# main.net
KiCad netlist of a schematic drawn in Altium Designer
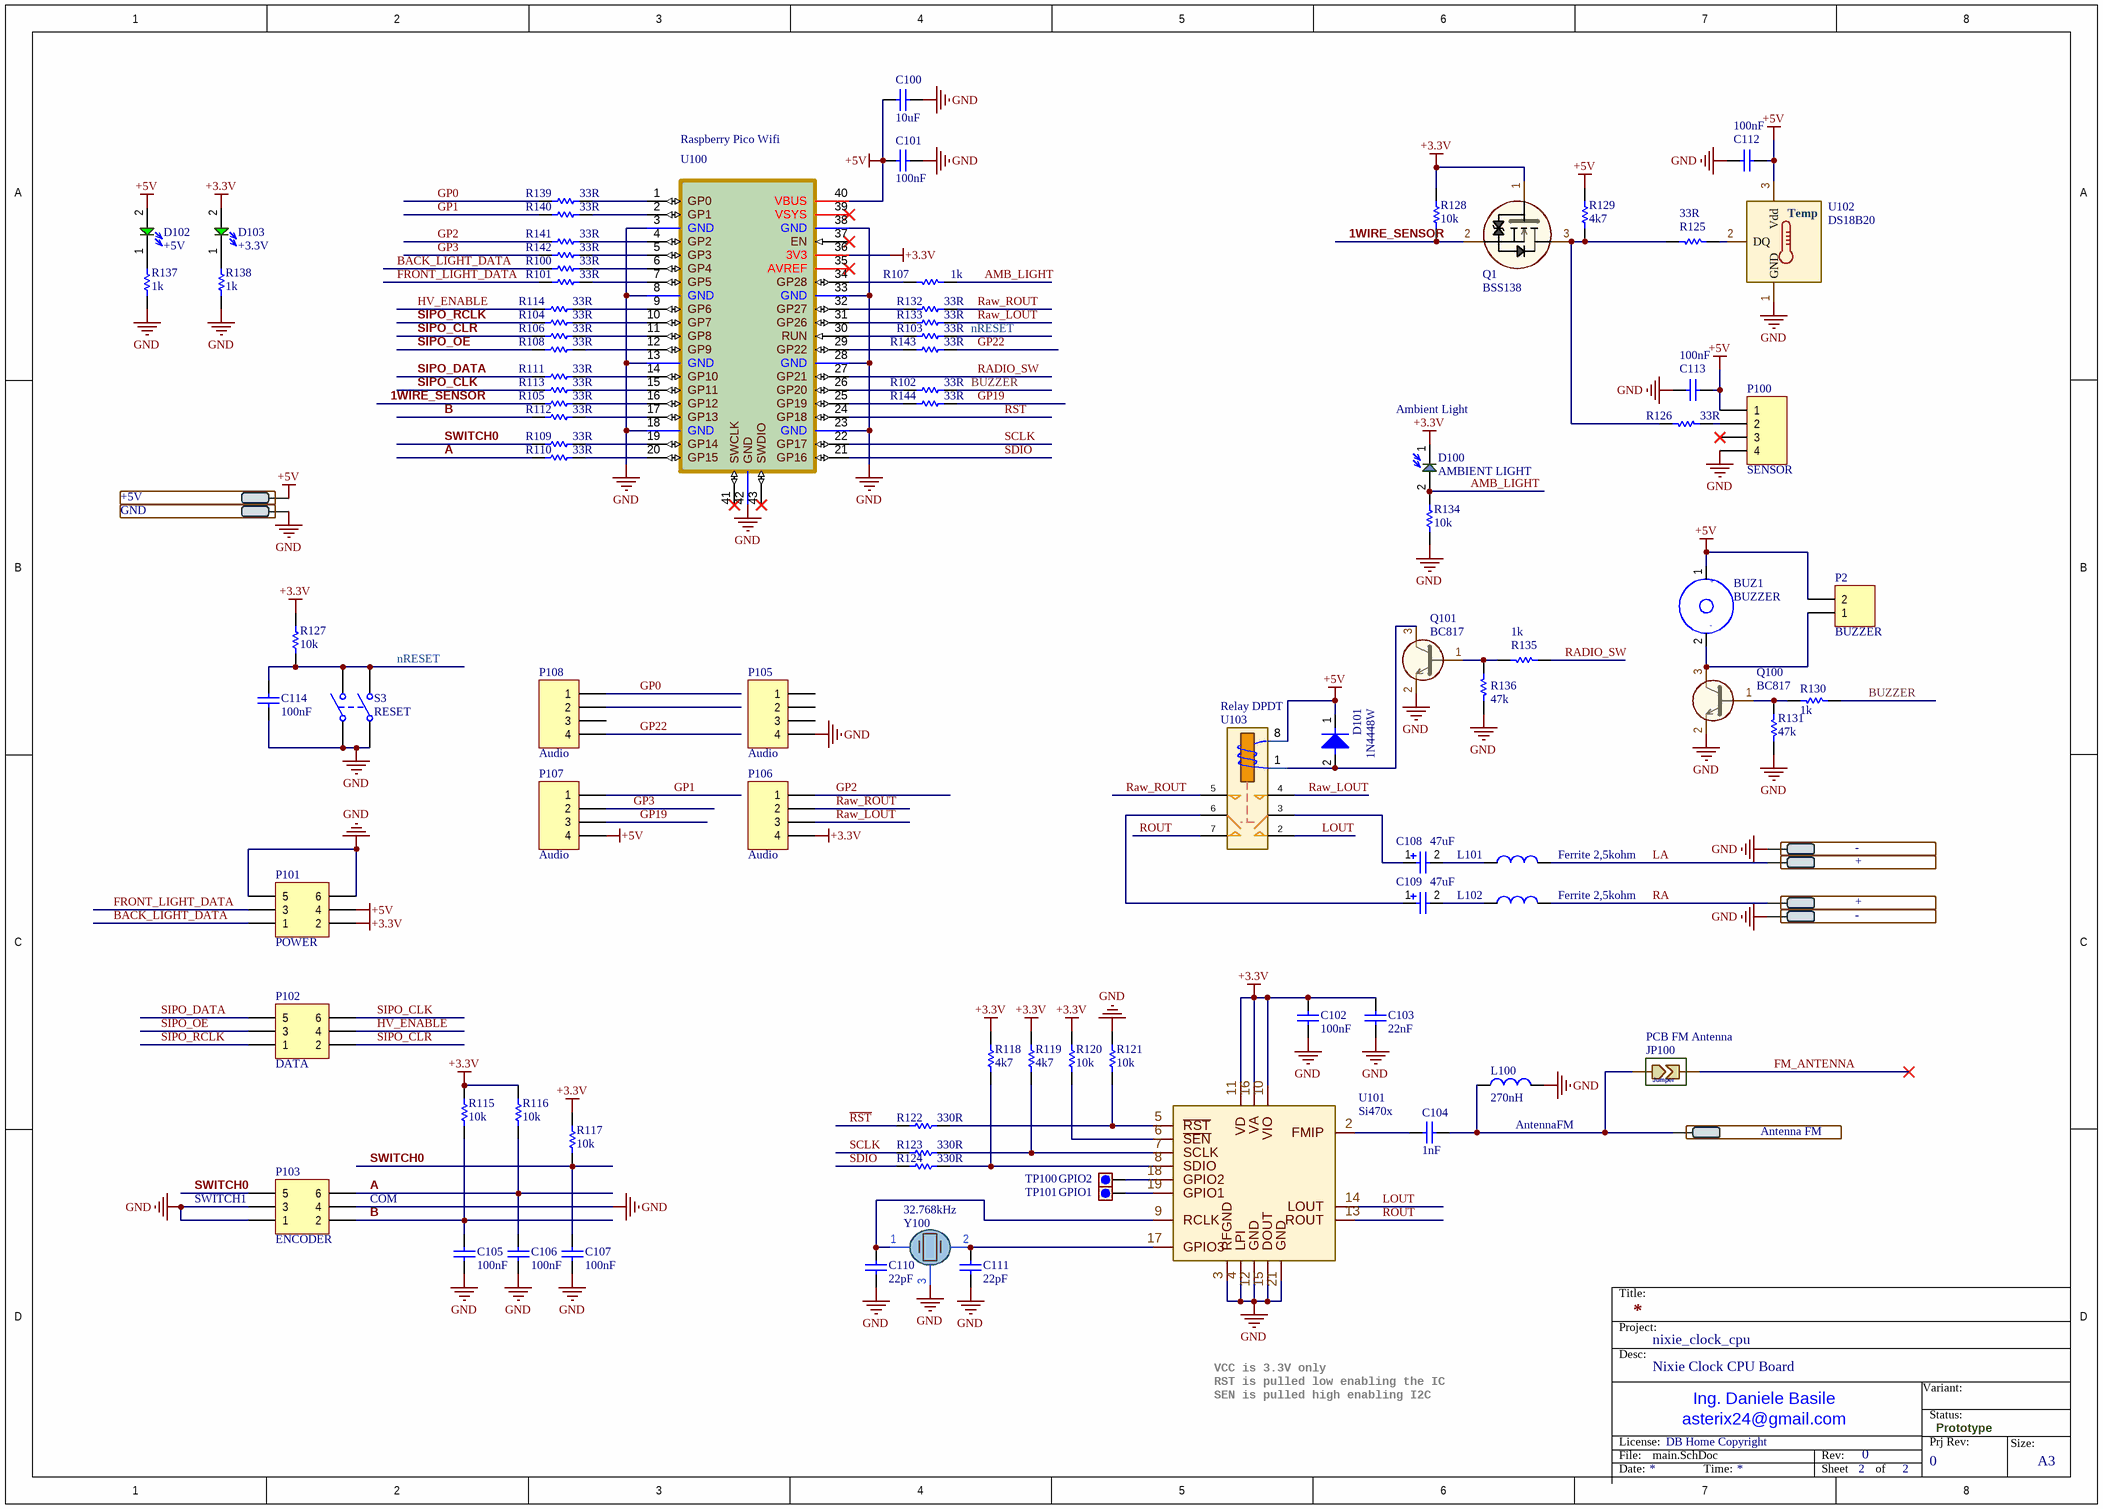
[diagram p0: main.SchDoc]

(export (version "E")
  (design (tool "Eeschema 10.0.6"))
  (components
    (comp (ref "BUZ1")
      (value "BUZZER")
      (footprint "buzzer_14mm_thd")
      (libsource (lib "develer_library") (part "BUZZER"))
    )
    (comp (ref "C100")
      (value "10uF")
      (footprint "0603_[1608]")
      (description "Capacitor")
      (libsource (lib "develer_generic") (part "Cap"))
    )
    (comp (ref "C101")
      (value "100nF")
      (footprint "0603_[1608]")
      (description "Capacitor")
      (libsource (lib "develer_generic") (part "Cap"))
    )
    (comp (ref "C102")
      (value "100nF")
      (footprint "0603_[1608]")
      (description "Capacitor")
      (libsource (lib "develer_generic") (part "Cap"))
    )
    (comp (ref "C103")
      (value "22nF")
      (footprint "0603_[1608]")
      (description "Capacitor")
      (libsource (lib "develer_generic") (part "Cap"))
    )
    (comp (ref "C104")
      (value "1nF")
      (footprint "0603_[1608]")
      (description "Capacitor")
      (libsource (lib "develer_generic") (part "Cap"))
    )
    (comp (ref "C105")
      (value "100nF")
      (footprint "0603_[1608]")
      (description "Capacitor")
      (libsource (lib "develer_generic") (part "Cap"))
    )
    (comp (ref "C106")
      (value "100nF")
      (footprint "0603_[1608]")
      (description "Capacitor")
      (libsource (lib "develer_generic") (part "Cap"))
    )
    (comp (ref "C107")
      (value "100nF")
      (footprint "0603_[1608]")
      (description "Capacitor")
      (libsource (lib "develer_generic") (part "Cap"))
    )
    (comp (ref "C108")
      (value "47uF")
      (footprint "[7343]_CAP_TAN_1P_2N")
      (description "Capacitor")
      (libsource (lib "develer_generic") (part "CapPol"))
    )
    (comp (ref "C109")
      (value "47uF")
      (footprint "[7343]_CAP_TAN_1P_2N")
      (description "Capacitor")
      (libsource (lib "develer_generic") (part "CapPol"))
    )
    (comp (ref "C110")
      (value "22pF")
      (footprint "0603_[1608]")
      (description "Capacitor")
      (libsource (lib "develer_generic") (part "Cap"))
    )
    (comp (ref "C111")
      (value "22pF")
      (footprint "0603_[1608]")
      (description "Capacitor")
      (libsource (lib "develer_generic") (part "Cap"))
    )
    (comp (ref "C112")
      (value "100nF")
      (footprint "0603_[1608]")
      (description "Capacitor")
      (libsource (lib "develer_generic") (part "Cap"))
    )
    (comp (ref "C113")
      (value "100nF")
      (footprint "0603_[1608]")
      (description "Capacitor")
      (libsource (lib "develer_generic") (part "Cap"))
    )
    (comp (ref "C114")
      (value "100nF")
      (footprint "0603_[1608]")
      (description "Capacitor")
      (libsource (lib "develer_generic") (part "Cap"))
    )
    (comp (ref "D100")
      (value "AMBIENT LIGHT")
      (footprint "R5_LED_THD_A2-K1")
      (description "Diode Led")
      (fields (field (name "PUBLISHER") "Develer srl"))
      (libsource (lib "develer_generic") (part "PhotoDiode"))
    )
    (comp (ref "D101")
      (value "1N4448W")
      (footprint "SOD-123_K1-A2")
      (description "Diode, Rectifier, 0,5A, 30V min (MBR230LSFT1G; Rohm RB070MM-30TR; panjin SBA130ASR100001)")
      (libsource (lib "develer_library") (part "Diode"))
    )
    (comp (ref "D102")
      (value "+5V")
      (footprint "0603_[1608]_K1-A2_LED")
      (description "Diode Led")
      (fields (field (name "PUBLISHER") "Develer srl"))
      (libsource (lib "develer_generic") (part "DiodeLedSmall_GREEN"))
    )
    (comp (ref "D103")
      (value "+3.3V")
      (footprint "0603_[1608]_K1-A2_LED")
      (description "Diode Led")
      (fields (field (name "PUBLISHER") "Develer srl"))
      (libsource (lib "develer_generic") (part "DiodeLedSmall_GREEN"))
    )
    (comp (ref "J100")
      (value "Antenna FM")
      (footprint "SMD_PIN_2x5MM")
      (description "Solder pad")
      (fields (field (name "PUBLISHER") "Develer srl"))
      (libsource (lib "develer_generic") (part "SolderPad"))
    )
    (comp (ref "J101")
      (value "-")
      (footprint "SMD_PIN_2x5MM")
      (description "Solder pad")
      (fields (field (name "PUBLISHER") "Develer srl"))
      (libsource (lib "develer_generic") (part "SolderPad"))
    )
    (comp (ref "J102")
      (value "+")
      (footprint "SMD_PIN_2x5MM")
      (description "Solder pad")
      (fields (field (name "PUBLISHER") "Develer srl"))
      (libsource (lib "develer_generic") (part "SolderPad"))
    )
    (comp (ref "J103")
      (value "+")
      (footprint "SMD_PIN_2x5MM")
      (description "Solder pad")
      (fields (field (name "PUBLISHER") "Develer srl"))
      (libsource (lib "develer_generic") (part "SolderPad"))
    )
    (comp (ref "J104")
      (value "-")
      (footprint "SMD_PIN_2x5MM")
      (description "Solder pad")
      (fields (field (name "PUBLISHER") "Develer srl"))
      (libsource (lib "develer_generic") (part "SolderPad"))
    )
    (comp (ref "J105")
      (value "+5V")
      (footprint "SMD_PIN_2x5MM")
      (description "Solder pad")
      (fields (field (name "PUBLISHER") "Develer srl"))
      (libsource (lib "develer_generic") (part "SolderPad"))
    )
    (comp (ref "J106")
      (value "GND")
      (footprint "SMD_PIN_2x5MM")
      (description "Solder pad")
      (fields (field (name "PUBLISHER") "Develer srl"))
      (libsource (lib "develer_generic") (part "SolderPad"))
    )
    (comp (ref "JP100")
      (value "PCB FM Antenna")
      (footprint "0603_[1608]_JUMPER")
      (description "Jumper SMD")
      (fields (field (name "PUBLISHER") "Develer srl"))
      (libsource (lib "develer_generic") (part "JumperSMD"))
    )
    (comp (ref "L100")
      (value "270nH")
      (footprint "0603_[1608]")
      (description "ComponetDescritions (altrenative1; alternativ2)")
      (fields (field (name "PUBLISHER") "Develer srl"))
      (libsource (lib "develer_generic") (part "Inductor"))
    )
    (comp (ref "L101")
      (value "Ferrite 2,5kohm")
      (footprint "0603_[1608]")
      (description "BLM18BD252SN1D")
      (fields (field (name "PUBLISHER") "Develer srl"))
      (libsource (lib "develer_generic") (part "Inductor"))
    )
    (comp (ref "L102")
      (value "Ferrite 2,5kohm")
      (footprint "0603_[1608]")
      (description "BLM18BD252SN1D")
      (fields (field (name "PUBLISHER") "Develer srl"))
      (libsource (lib "develer_generic") (part "Inductor"))
    )
    (comp (ref "P2")
      (value "BUZZER")
      (footprint "HEADER_1X2_2.54MM_THD")
      (description "Pin Header, 2pin, 2.54mm")
      (fields (field (name "PUBLISHER") "Altium Limited"))
      (libsource (lib "Miscellaneous Connectors") (part "Header 2"))
    )
    (comp (ref "P100")
      (value "SENSOR")
      (footprint "HEADER_1X4_2.54MM_THD")
      (description "Header, 4-Pin")
      (fields (field (name "PUBLISHER") "Altium Limited"))
      (libsource (lib "Miscellaneous Connectors") (part "Header 4"))
    )
    (comp (ref "P101")
      (value "POWER")
      (footprint "SOCKET_2x3_2.54mm_THD")
      (description "Header, 3-Pin, Dual row")
      (fields (field (name "PUBLISHER") "Altium Limited"))
      (libsource (lib "Miscellaneous Connectors") (part "Header 3X2"))
    )
    (comp (ref "P102")
      (value "DATA")
      (footprint "SOCKET_2x3_2.54mm_THD")
      (description "Header, 3-Pin, Dual row")
      (fields (field (name "PUBLISHER") "Altium Limited"))
      (libsource (lib "Miscellaneous Connectors") (part "Header 3X2"))
    )
    (comp (ref "P103")
      (value "ENCODER")
      (footprint "SOCKET_2x3_2.54mm_THD")
      (description "Header, 3-Pin, Dual row")
      (fields (field (name "PUBLISHER") "Altium Limited"))
      (libsource (lib "Miscellaneous Connectors") (part "Header 3X2"))
    )
    (comp (ref "P105")
      (value "Audio")
      (footprint "HEADER_1X4_2.54MM_THD")
      (description "Header, 4-Pin")
      (fields (field (name "PUBLISHER") "Altium Limited"))
      (libsource (lib "") (part "Header 4_1"))
    )
    (comp (ref "P106")
      (value "Audio")
      (footprint "HEADER_1X4_2.54MM_THD")
      (description "Header, 4-Pin")
      (fields (field (name "PUBLISHER") "Altium Limited"))
      (libsource (lib "") (part "Header 4_1"))
    )
    (comp (ref "P107")
      (value "Audio")
      (footprint "HEADER_1X4_2.54MM_THD")
      (description "Header, 4-Pin")
      (fields (field (name "PUBLISHER") "Altium Limited"))
      (libsource (lib "") (part "Header 4_1"))
    )
    (comp (ref "P108")
      (value "Audio")
      (footprint "HEADER_1X4_2.54MM_THD")
      (description "Header, 4-Pin")
      (fields (field (name "PUBLISHER") "Altium Limited"))
      (libsource (lib "") (part "Header 4_1"))
    )
    (comp (ref "Q1")
      (value "BSS138")
      (footprint "SOT-23")
      (description "N-MOSFET 50V 0,22A")
      (fields (field (name "PUBLISHER") "Develer srl"))
      (libsource (lib "develer_components") (part "BSS138"))
    )
    (comp (ref "Q100")
      (value "BC817")
      (footprint "SOT-23")
      (description "Transistor BJT NPN")
      (fields (field (name "PUBLISHER") "Develer srl"))
      (libsource (lib "develer_generic") (part "NPN_3P"))
    )
    (comp (ref "Q101")
      (value "BC817")
      (footprint "SOT-23")
      (description "Transistor BJT NPN")
      (fields (field (name "PUBLISHER") "Develer srl"))
      (libsource (lib "develer_generic") (part "NPN_3P"))
    )
    (comp (ref "R100")
      (value "33R")
      (footprint "0603_[1608]")
      (description "Resistor")
      (fields (field (name "PUBLISHER") "Develer srl"))
      (libsource (lib "develer_generic") (part "Res"))
    )
    (comp (ref "R101")
      (value "33R")
      (footprint "0603_[1608]")
      (description "Resistor")
      (fields (field (name "PUBLISHER") "Develer srl"))
      (libsource (lib "develer_generic") (part "Res"))
    )
    (comp (ref "R102")
      (value "33R")
      (footprint "0603_[1608]")
      (description "Resistor")
      (fields (field (name "PUBLISHER") "Develer srl"))
      (libsource (lib "develer_generic") (part "Res"))
    )
    (comp (ref "R103")
      (value "33R")
      (footprint "0603_[1608]")
      (description "Resistor")
      (fields (field (name "PUBLISHER") "Develer srl"))
      (libsource (lib "develer_generic") (part "Res"))
    )
    (comp (ref "R104")
      (value "33R")
      (footprint "0603_[1608]")
      (description "Resistor")
      (fields (field (name "PUBLISHER") "Develer srl"))
      (libsource (lib "develer_generic") (part "Res"))
    )
    (comp (ref "R105")
      (value "33R")
      (footprint "0603_[1608]")
      (description "Resistor")
      (fields (field (name "PUBLISHER") "Develer srl"))
      (libsource (lib "develer_generic") (part "Res"))
    )
    (comp (ref "R106")
      (value "33R")
      (footprint "0603_[1608]")
      (description "Resistor")
      (fields (field (name "PUBLISHER") "Develer srl"))
      (libsource (lib "develer_generic") (part "Res"))
    )
    (comp (ref "R107")
      (value "1k")
      (footprint "0603_[1608]")
      (description "Resistor")
      (fields (field (name "PUBLISHER") "Develer srl"))
      (libsource (lib "develer_generic") (part "Res"))
    )
    (comp (ref "R108")
      (value "33R")
      (footprint "0603_[1608]")
      (description "Resistor")
      (fields (field (name "PUBLISHER") "Develer srl"))
      (libsource (lib "develer_generic") (part "Res"))
    )
    (comp (ref "R109")
      (value "33R")
      (footprint "0603_[1608]")
      (description "Resistor")
      (fields (field (name "PUBLISHER") "Develer srl"))
      (libsource (lib "develer_generic") (part "Res"))
    )
    (comp (ref "R110")
      (value "33R")
      (footprint "0603_[1608]")
      (description "Resistor")
      (fields (field (name "PUBLISHER") "Develer srl"))
      (libsource (lib "develer_generic") (part "Res"))
    )
    (comp (ref "R111")
      (value "33R")
      (footprint "0603_[1608]")
      (description "Resistor")
      (fields (field (name "PUBLISHER") "Develer srl"))
      (libsource (lib "develer_generic") (part "Res"))
    )
    (comp (ref "R112")
      (value "33R")
      (footprint "0603_[1608]")
      (description "Resistor")
      (fields (field (name "PUBLISHER") "Develer srl"))
      (libsource (lib "develer_generic") (part "Res"))
    )
    (comp (ref "R113")
      (value "33R")
      (footprint "0603_[1608]")
      (description "Resistor")
      (fields (field (name "PUBLISHER") "Develer srl"))
      (libsource (lib "develer_generic") (part "Res"))
    )
    (comp (ref "R114")
      (value "33R")
      (footprint "0603_[1608]")
      (description "Resistor")
      (fields (field (name "PUBLISHER") "Develer srl"))
      (libsource (lib "develer_generic") (part "Res"))
    )
    (comp (ref "R115")
      (value "10k")
      (footprint "0603_[1608]")
      (description "Resistor")
      (fields (field (name "PUBLISHER") "Develer srl"))
      (libsource (lib "develer_generic") (part "Res"))
    )
    (comp (ref "R116")
      (value "10k")
      (footprint "0603_[1608]")
      (description "Resistor")
      (fields (field (name "PUBLISHER") "Develer srl"))
      (libsource (lib "develer_generic") (part "Res"))
    )
    (comp (ref "R117")
      (value "10k")
      (footprint "0603_[1608]")
      (description "Resistor")
      (fields (field (name "PUBLISHER") "Develer srl"))
      (libsource (lib "develer_generic") (part "Res"))
    )
    (comp (ref "R118")
      (value "4k7")
      (footprint "0603_[1608]")
      (description "Resistor")
      (fields (field (name "PUBLISHER") "Develer srl"))
      (libsource (lib "develer_generic") (part "Res"))
    )
    (comp (ref "R119")
      (value "4k7")
      (footprint "0603_[1608]")
      (description "Resistor")
      (fields (field (name "PUBLISHER") "Develer srl"))
      (libsource (lib "develer_generic") (part "Res"))
    )
    (comp (ref "R120")
      (value "10k")
      (footprint "0603_[1608]")
      (description "Resistor")
      (fields (field (name "PUBLISHER") "Develer srl"))
      (libsource (lib "develer_generic") (part "Res"))
    )
    (comp (ref "R121")
      (value "10k")
      (footprint "0603_[1608]")
      (description "Resistor")
      (fields (field (name "PUBLISHER") "Develer srl"))
      (libsource (lib "develer_generic") (part "Res"))
    )
    (comp (ref "R122")
      (value "330R")
      (footprint "0603_[1608]")
      (description "Resistor")
      (fields (field (name "PUBLISHER") "Develer srl"))
      (libsource (lib "develer_generic") (part "Res"))
    )
    (comp (ref "R123")
      (value "330R")
      (footprint "0603_[1608]")
      (description "Resistor")
      (fields (field (name "PUBLISHER") "Develer srl"))
      (libsource (lib "develer_generic") (part "Res"))
    )
    (comp (ref "R124")
      (value "330R")
      (footprint "0603_[1608]")
      (description "Resistor")
      (fields (field (name "PUBLISHER") "Develer srl"))
      (libsource (lib "develer_generic") (part "Res"))
    )
    (comp (ref "R125")
      (value "33R")
      (footprint "0603_[1608]")
      (description "Resistor")
      (fields (field (name "PUBLISHER") "Develer srl"))
      (libsource (lib "develer_generic") (part "Res"))
    )
    (comp (ref "R126")
      (value "33R")
      (footprint "0603_[1608]")
      (description "Resistor")
      (fields (field (name "PUBLISHER") "Develer srl"))
      (libsource (lib "develer_generic") (part "Res"))
    )
    (comp (ref "R127")
      (value "10k")
      (footprint "0603_[1608]")
      (description "Resistor")
      (fields (field (name "PUBLISHER") "Develer srl"))
      (libsource (lib "develer_generic") (part "Res"))
    )
    (comp (ref "R128")
      (value "10k")
      (footprint "0603_[1608]")
      (description "Resistor")
      (fields (field (name "PUBLISHER") "Develer srl"))
      (libsource (lib "develer_generic") (part "Res"))
    )
    (comp (ref "R129")
      (value "4k7")
      (footprint "0603_[1608]")
      (description "Resistor")
      (fields (field (name "PUBLISHER") "Develer srl"))
      (libsource (lib "develer_generic") (part "Res"))
    )
    (comp (ref "R130")
      (value "1k")
      (footprint "0603_[1608]")
      (description "Resistor")
      (fields (field (name "PUBLISHER") "Develer srl"))
      (libsource (lib "develer_generic") (part "Res"))
    )
    (comp (ref "R131")
      (value "47k")
      (footprint "0603_[1608]")
      (description "Resistor")
      (fields (field (name "PUBLISHER") "Develer srl"))
      (libsource (lib "develer_generic") (part "Res"))
    )
    (comp (ref "R132")
      (value "33R")
      (footprint "0603_[1608]")
      (description "Resistor")
      (fields (field (name "PUBLISHER") "Develer srl"))
      (libsource (lib "develer_generic") (part "Res"))
    )
    (comp (ref "R133")
      (value "33R")
      (footprint "0603_[1608]")
      (description "Resistor")
      (fields (field (name "PUBLISHER") "Develer srl"))
      (libsource (lib "develer_generic") (part "Res"))
    )
    (comp (ref "R134")
      (value "10k")
      (footprint "0603_[1608]")
      (description "Resistor")
      (fields (field (name "PUBLISHER") "Develer srl"))
      (libsource (lib "develer_generic") (part "Res"))
    )
    (comp (ref "R135")
      (value "1k")
      (footprint "0603_[1608]")
      (description "Resistor")
      (fields (field (name "PUBLISHER") "Develer srl"))
      (libsource (lib "develer_generic") (part "Res"))
    )
    (comp (ref "R136")
      (value "47k")
      (footprint "0603_[1608]")
      (description "Resistor")
      (fields (field (name "PUBLISHER") "Develer srl"))
      (libsource (lib "develer_generic") (part "Res"))
    )
    (comp (ref "R137")
      (value "1k")
      (footprint "0603_[1608]")
      (description "Resistor")
      (fields (field (name "PUBLISHER") "Develer srl"))
      (libsource (lib "develer_generic") (part "Res"))
    )
    (comp (ref "R138")
      (value "1k")
      (footprint "0603_[1608]")
      (description "Resistor")
      (fields (field (name "PUBLISHER") "Develer srl"))
      (libsource (lib "develer_generic") (part "Res"))
    )
    (comp (ref "R139")
      (value "33R")
      (footprint "0603_[1608]")
      (description "Resistor")
      (fields (field (name "PUBLISHER") "Develer srl"))
      (libsource (lib "develer_generic") (part "Res"))
    )
    (comp (ref "R140")
      (value "33R")
      (footprint "0603_[1608]")
      (description "Resistor")
      (fields (field (name "PUBLISHER") "Develer srl"))
      (libsource (lib "develer_generic") (part "Res"))
    )
    (comp (ref "R141")
      (value "33R")
      (footprint "0603_[1608]")
      (description "Resistor")
      (fields (field (name "PUBLISHER") "Develer srl"))
      (libsource (lib "develer_generic") (part "Res"))
    )
    (comp (ref "R142")
      (value "33R")
      (footprint "0603_[1608]")
      (description "Resistor")
      (fields (field (name "PUBLISHER") "Develer srl"))
      (libsource (lib "develer_generic") (part "Res"))
    )
    (comp (ref "R143")
      (value "33R")
      (footprint "0603_[1608]")
      (description "Resistor")
      (fields (field (name "PUBLISHER") "Develer srl"))
      (libsource (lib "develer_generic") (part "Res"))
    )
    (comp (ref "R144")
      (value "33R")
      (footprint "0603_[1608]")
      (description "Resistor")
      (fields (field (name "PUBLISHER") "Develer srl"))
      (libsource (lib "develer_generic") (part "Res"))
    )
    (comp (ref "S3")
      (value "RESET")
      (footprint "TACTILE_SWITCH_6x6MM_THD")
      (description "Double-Pole, Single-Throw Switch")
      (fields (field (name "PUBLISHER") "Altium Limited"))
      (libsource (lib "develer_generic") (part "Switch DPST"))
    )
    (comp (ref "TP100")
      (value "GPIO2")
      (footprint "TEST_POINT_THD_D1.6MM")
      (description "TestPoint")
      (fields (field (name "PUBLISHER") "Develer srl"))
      (libsource (lib "develer_generic") (part "TestPoint"))
    )
    (comp (ref "TP101")
      (value "GPIO1")
      (footprint "TEST_POINT_THD_D1.6MM")
      (description "TestPoint")
      (fields (field (name "PUBLISHER") "Develer srl"))
      (libsource (lib "develer_generic") (part "TestPoint"))
    )
    (comp (ref "U100")
      (value "Raspberry Pico Wifi")
      (footprint "RasberryPicoMod")
      (description "Raspberry PICO som module")
      (fields (field (name "PUBLISHER") "Develer srl"))
      (libsource (lib "develer_components") (part "RaspberryPico_Mod"))
    )
    (comp (ref "U101")
      (value "Si470x")
      (footprint "QFN-50P-20_PAD")
      (description "Full FM radio whit RDS")
      (fields (field (name "PUBLISHER") "Develer srl"))
      (libsource (lib "develer_components") (part "Si470x"))
    )
    (comp (ref "U102")
      (value "DS18B20")
      (footprint "develer_misc:TO-92")
      (description "Programmable Resolution 1-Wire Digital Thermometer")
      (fields (field (name "PUBLISHER") "Develer srl"))
      (libsource (lib "develer_components") (part "DS18B20"))
    )
    (comp (ref "U103")
      (value "Relay DPDT")
      (footprint "RELAYS_DPST_THD_6x10_5.08mm")
      (fields (field (name "PUBLISHER") "Develer srl"))
      (libsource (lib "develer_generic") (part "Relay2_DPDT"))
    )
    (comp (ref "Y100")
      (value "32.768kHz")
      (footprint "CRISTAL_R26_PAD")
      (description "ComponentDescriptions (altrenative1; alternative2)")
      (fields (field (name "PUBLISHER") "Develer srl"))
      (libsource (lib "develer_generic") (part "Cristal_3P"))
    )
  )
  (nets
    (net (code "1") (name "+3.3V") (class "Default")
      (node (ref "C102") (pin "2") (pinfunction "2_2") (pintype "passive"))
      (node (ref "C103") (pin "2") (pinfunction "2_2") (pintype "passive"))
      (node (ref "D100") (pin "1") (pinfunction "K_1") (pintype "passive"))
      (node (ref "D103") (pin "2") (pinfunction "A_2") (pintype "passive"))
      (node (ref "P101") (pin "2") (pinfunction "2_2") (pintype "passive"))
      (node (ref "P106") (pin "4") (pinfunction "4_4") (pintype "passive"))
      (node (ref "Q1") (pin "1") (pinfunction "G_1") (pintype "passive"))
      (node (ref "R115") (pin "1") (pinfunction "1_1") (pintype "passive"))
      (node (ref "R116") (pin "1") (pinfunction "1_1") (pintype "passive"))
      (node (ref "R117") (pin "1") (pinfunction "1_1") (pintype "passive"))
      (node (ref "R118") (pin "1") (pinfunction "1_1") (pintype "passive"))
      (node (ref "R119") (pin "1") (pinfunction "1_1") (pintype "passive"))
      (node (ref "R120") (pin "1") (pinfunction "1_1") (pintype "passive"))
      (node (ref "R127") (pin "1") (pinfunction "1_1") (pintype "passive"))
      (node (ref "R128") (pin "1") (pinfunction "1_1") (pintype "passive"))
      (node (ref "U100") (pin "36") (pinfunction "3V3_36") (pintype "power_in"))
      (node (ref "U101") (pin "10") (pinfunction "VIO_10") (pintype "passive"))
      (node (ref "U101") (pin "11") (pinfunction "VD_11") (pintype "passive"))
      (node (ref "U101") (pin "16") (pinfunction "VA_16") (pintype "passive"))
    )
    (net (code "2") (name "+5V") (class "Default")
      (node (ref "BUZ1") (pin "1") (pinfunction "1_1") (pintype "passive"))
      (node (ref "C100") (pin "1") (pinfunction "1_1") (pintype "passive"))
      (node (ref "C101") (pin "1") (pinfunction "1_1") (pintype "passive"))
      (node (ref "C112") (pin "1") (pinfunction "1_1") (pintype "passive"))
      (node (ref "C113") (pin "1") (pinfunction "1_1") (pintype "passive"))
      (node (ref "D101") (pin "1") (pinfunction "K_1") (pintype "passive"))
      (node (ref "D102") (pin "2") (pinfunction "A_2") (pintype "passive"))
      (node (ref "J105") (pin "1") (pinfunction "1_1") (pintype "passive"))
      (node (ref "P100") (pin "1") (pinfunction "1_1") (pintype "passive"))
      (node (ref "P101") (pin "4") (pinfunction "4_4") (pintype "passive"))
      (node (ref "P107") (pin "4") (pinfunction "4_4") (pintype "passive"))
      (node (ref "P2") (pin "2") (pinfunction "2_2") (pintype "passive"))
      (node (ref "R129") (pin "1") (pinfunction "1_1") (pintype "passive"))
      (node (ref "U100") (pin "40") (pinfunction "VBUS_40") (pintype "power_in"))
      (node (ref "U102") (pin "3") (pinfunction "Vdd_3") (pintype "passive"))
      (node (ref "U103") (pin "8") (pinfunction "8_8") (pintype "passive"))
    )
    (net (code "3") (name "/1WIRE_SENSOR") (class "Default")
      (node (ref "Q1") (pin "2") (pinfunction "S_2") (pintype "passive"))
      (node (ref "R105") (pin "2") (pinfunction "2_2") (pintype "passive"))
      (node (ref "R128") (pin "2") (pinfunction "2_2") (pintype "passive"))
    )
    (net (code "4") (name "/A") (class "Default")
      (node (ref "C106") (pin "2") (pinfunction "2_2") (pintype "passive"))
      (node (ref "P103") (pin "6") (pinfunction "6_6") (pintype "passive"))
      (node (ref "R110") (pin "2") (pinfunction "2_2") (pintype "passive"))
      (node (ref "R116") (pin "2") (pinfunction "2_2") (pintype "passive"))
    )
    (net (code "5") (name "/AMB_LIGHT") (class "Default")
      (node (ref "D100") (pin "2") (pinfunction "A_2") (pintype "passive"))
      (node (ref "R107") (pin "1") (pinfunction "1_1") (pintype "passive"))
      (node (ref "R134") (pin "1") (pinfunction "1_1") (pintype "passive"))
    )
    (net (code "6") (name "/B") (class "Default")
      (node (ref "C105") (pin "2") (pinfunction "2_2") (pintype "passive"))
      (node (ref "P103") (pin "2") (pinfunction "2_2") (pintype "passive"))
      (node (ref "R112") (pin "2") (pinfunction "2_2") (pintype "passive"))
      (node (ref "R115") (pin "2") (pinfunction "2_2") (pintype "passive"))
    )
    (net (code "7") (name "/BACK_LIGHT_DATA") (class "Default")
      (node (ref "P101") (pin "1") (pinfunction "1_1") (pintype "passive"))
      (node (ref "R100") (pin "2") (pinfunction "2_2") (pintype "passive"))
    )
    (net (code "8") (name "/BUZZER") (class "Default")
      (node (ref "R102") (pin "1") (pinfunction "1_1") (pintype "passive"))
      (node (ref "R130") (pin "1") (pinfunction "1_1") (pintype "passive"))
    )
    (net (code "9") (name "/FM_ANTENNA") (class "Default")
      (node (ref "JP100") (pin "2") (pinfunction "2_2") (pintype "passive+no_connect"))
    )
    (net (code "10") (name "/FRONT_LIGHT_DATA") (class "Default")
      (node (ref "P101") (pin "3") (pinfunction "3_3") (pintype "passive"))
      (node (ref "R101") (pin "2") (pinfunction "2_2") (pintype "passive"))
    )
    (net (code "11") (name "/GP0") (class "Default")
      (node (ref "P108") (pin "1") (pinfunction "1_1") (pintype "passive"))
      (node (ref "R139") (pin "2") (pinfunction "2_2") (pintype "passive"))
    )
    (net (code "12") (name "/GP1") (class "Default")
      (node (ref "P107") (pin "1") (pinfunction "1_1") (pintype "passive"))
      (node (ref "R140") (pin "2") (pinfunction "2_2") (pintype "passive"))
    )
    (net (code "13") (name "/GP2") (class "Default")
      (node (ref "P106") (pin "1") (pinfunction "1_1") (pintype "passive"))
      (node (ref "R141") (pin "2") (pinfunction "2_2") (pintype "passive"))
    )
    (net (code "14") (name "/GP3") (class "Default")
      (node (ref "P107") (pin "2") (pinfunction "2_2") (pintype "passive"))
      (node (ref "R142") (pin "2") (pinfunction "2_2") (pintype "passive"))
    )
    (net (code "15") (name "/GP19") (class "Default")
      (node (ref "P107") (pin "3") (pinfunction "3_3") (pintype "passive"))
      (node (ref "R144") (pin "1") (pinfunction "1_1") (pintype "passive"))
    )
    (net (code "16") (name "/GP22") (class "Default")
      (node (ref "P108") (pin "4") (pinfunction "4_4") (pintype "passive"))
      (node (ref "R143") (pin "1") (pinfunction "1_1") (pintype "passive"))
    )
    (net (code "17") (name "/HV_ENABLE") (class "Default")
      (node (ref "P102") (pin "4") (pinfunction "4_4") (pintype "passive"))
      (node (ref "R114") (pin "2") (pinfunction "2_2") (pintype "passive"))
    )
    (net (code "18") (name "/LA") (class "Default")
      (node (ref "J102") (pin "1") (pinfunction "1_1") (pintype "passive"))
      (node (ref "L101") (pin "2") (pinfunction "2_2") (pintype "passive"))
    )
    (net (code "19") (name "/LOUT") (class "Default")
      (node (ref "U101") (pin "14") (pinfunction "LOUT_14") (pintype "passive"))
      (node (ref "U103") (pin "2") (pinfunction "2_2") (pintype "passive"))
    )
    (net (code "20") (name "/RA") (class "Default")
      (node (ref "J103") (pin "1") (pinfunction "1_1") (pintype "passive"))
      (node (ref "L102") (pin "2") (pinfunction "2_2") (pintype "passive"))
    )
    (net (code "21") (name "/RADIO_SW") (class "Default")
      (node (ref "R135") (pin "1") (pinfunction "1_1") (pintype "passive"))
      (node (ref "U100") (pin "27") (pinfunction "GP21_27") (pintype "bidirectional"))
    )
    (net (code "22") (name "/ROUT") (class "Default")
      (node (ref "U101") (pin "13") (pinfunction "ROUT_13") (pintype "passive"))
      (node (ref "U103") (pin "7") (pinfunction "7_7") (pintype "passive"))
    )
    (net (code "23") (name "/Raw_LOUT") (class "Default")
      (node (ref "P106") (pin "3") (pinfunction "3_3") (pintype "passive"))
      (node (ref "R133") (pin "1") (pinfunction "1_1") (pintype "passive"))
      (node (ref "U103") (pin "4") (pinfunction "4_4") (pintype "passive"))
    )
    (net (code "24") (name "/Raw_ROUT") (class "Default")
      (node (ref "P106") (pin "2") (pinfunction "2_2") (pintype "passive"))
      (node (ref "R132") (pin "1") (pinfunction "1_1") (pintype "passive"))
      (node (ref "U103") (pin "5") (pinfunction "5_5") (pintype "passive"))
    )
    (net (code "25") (name "/SCLK") (class "Default")
      (node (ref "R123") (pin "2") (pinfunction "2_2") (pintype "passive"))
      (node (ref "U100") (pin "22") (pinfunction "GP17_22") (pintype "bidirectional"))
    )
    (net (code "26") (name "/SDIO") (class "Default")
      (node (ref "R124") (pin "2") (pinfunction "2_2") (pintype "passive"))
      (node (ref "U100") (pin "21") (pinfunction "GP16_21") (pintype "bidirectional"))
    )
    (net (code "27") (name "/SIPO_CLK") (class "Default")
      (node (ref "P102") (pin "6") (pinfunction "6_6") (pintype "passive"))
      (node (ref "R113") (pin "2") (pinfunction "2_2") (pintype "passive"))
    )
    (net (code "28") (name "/SIPO_CLR") (class "Default")
      (node (ref "P102") (pin "2") (pinfunction "2_2") (pintype "passive"))
      (node (ref "R106") (pin "2") (pinfunction "2_2") (pintype "passive"))
    )
    (net (code "29") (name "/SIPO_DATA") (class "Default")
      (node (ref "P102") (pin "5") (pinfunction "5_5") (pintype "passive"))
      (node (ref "R111") (pin "2") (pinfunction "2_2") (pintype "passive"))
    )
    (net (code "30") (name "/SIPO_OE") (class "Default")
      (node (ref "P102") (pin "3") (pinfunction "3_3") (pintype "passive"))
      (node (ref "R108") (pin "2") (pinfunction "2_2") (pintype "passive"))
    )
    (net (code "31") (name "/SIPO_RCLK") (class "Default")
      (node (ref "P102") (pin "1") (pinfunction "1_1") (pintype "passive"))
      (node (ref "R104") (pin "2") (pinfunction "2_2") (pintype "passive"))
    )
    (net (code "32") (name "/SWITCH0") (class "Default")
      (node (ref "C107") (pin "2") (pinfunction "2_2") (pintype "passive"))
      (node (ref "P103") (pin "5") (pinfunction "5_5") (pintype "passive"))
      (node (ref "R109") (pin "2") (pinfunction "2_2") (pintype "passive"))
      (node (ref "R117") (pin "2") (pinfunction "2_2") (pintype "passive"))
    )
    (net (code "33") (name "/nRESET") (class "Default")
      (node (ref "C114") (pin "2") (pinfunction "2_2") (pintype "passive"))
      (node (ref "R103") (pin "1") (pinfunction "1_1") (pintype "passive"))
      (node (ref "R127") (pin "2") (pinfunction "2_2") (pintype "passive"))
      (node (ref "S3") (pin "3") (pinfunction "NO1_3") (pintype "passive"))
      (node (ref "S3") (pin "4") (pinfunction "NO2_4") (pintype "passive"))
    )
    (net (code "34") (name "/~{RST}") (class "Default")
      (node (ref "R122") (pin "2") (pinfunction "2_2") (pintype "passive"))
      (node (ref "U100") (pin "24") (pinfunction "GP18_24") (pintype "bidirectional"))
    )
    (net (code "35") (name "GND") (class "Default")
      (node (ref "C100") (pin "2") (pinfunction "2_2") (pintype "passive"))
      (node (ref "C101") (pin "2") (pinfunction "2_2") (pintype "passive"))
      (node (ref "C102") (pin "1") (pinfunction "1_1") (pintype "passive"))
      (node (ref "C103") (pin "1") (pinfunction "1_1") (pintype "passive"))
      (node (ref "C105") (pin "1") (pinfunction "1_1") (pintype "passive"))
      (node (ref "C106") (pin "1") (pinfunction "1_1") (pintype "passive"))
      (node (ref "C107") (pin "1") (pinfunction "1_1") (pintype "passive"))
      (node (ref "C110") (pin "1") (pinfunction "1_1") (pintype "passive"))
      (node (ref "C111") (pin "1") (pinfunction "1_1") (pintype "passive"))
      (node (ref "C112") (pin "2") (pinfunction "2_2") (pintype "passive"))
      (node (ref "C113") (pin "2") (pinfunction "2_2") (pintype "passive"))
      (node (ref "C114") (pin "1") (pinfunction "1_1") (pintype "passive"))
      (node (ref "J101") (pin "1") (pinfunction "1_1") (pintype "passive"))
      (node (ref "J104") (pin "1") (pinfunction "1_1") (pintype "passive"))
      (node (ref "J106") (pin "1") (pinfunction "1_1") (pintype "passive"))
      (node (ref "L100") (pin "2") (pinfunction "2_2") (pintype "passive"))
      (node (ref "P100") (pin "4") (pinfunction "4_4") (pintype "passive"))
      (node (ref "P101") (pin "5") (pinfunction "5_5") (pintype "passive"))
      (node (ref "P101") (pin "6") (pinfunction "6_6") (pintype "passive"))
      (node (ref "P103") (pin "1") (pinfunction "1_1") (pintype "passive"))
      (node (ref "P103") (pin "3") (pinfunction "3_3") (pintype "passive"))
      (node (ref "P103") (pin "4") (pinfunction "4_4") (pintype "passive"))
      (node (ref "P105") (pin "4") (pinfunction "4_4") (pintype "passive"))
      (node (ref "Q100") (pin "2") (pinfunction "2_2") (pintype "passive"))
      (node (ref "Q101") (pin "2") (pinfunction "2_2") (pintype "passive"))
      (node (ref "R121") (pin "1") (pinfunction "1_1") (pintype "passive"))
      (node (ref "R131") (pin "1") (pinfunction "1_1") (pintype "passive"))
      (node (ref "R134") (pin "2") (pinfunction "2_2") (pintype "passive"))
      (node (ref "R136") (pin "1") (pinfunction "1_1") (pintype "passive"))
      (node (ref "R137") (pin "1") (pinfunction "1_1") (pintype "passive"))
      (node (ref "R138") (pin "1") (pinfunction "1_1") (pintype "passive"))
      (node (ref "S3") (pin "1") (pinfunction "COMMON1_1") (pintype "passive"))
      (node (ref "S3") (pin "2") (pinfunction "COMMON2_2") (pintype "passive"))
      (node (ref "U100") (pin "13") (pinfunction "GND_13") (pintype "power_in"))
      (node (ref "U100") (pin "18") (pinfunction "GND_18") (pintype "power_in"))
      (node (ref "U100") (pin "23") (pinfunction "GND_23") (pintype "power_in"))
      (node (ref "U100") (pin "28") (pinfunction "GND_28") (pintype "power_in"))
      (node (ref "U100") (pin "3") (pinfunction "GND_3") (pintype "power_in"))
      (node (ref "U100") (pin "33") (pinfunction "GND_33") (pintype "power_in"))
      (node (ref "U100") (pin "38") (pinfunction "GND_38") (pintype "power_in"))
      (node (ref "U100") (pin "42") (pinfunction "GND_42") (pintype "power_in"))
      (node (ref "U100") (pin "8") (pinfunction "GND_8") (pintype "power_in"))
      (node (ref "U101") (pin "12") (pinfunction "GND_12") (pintype "passive"))
      (node (ref "U101") (pin "15") (pinfunction "DOUT_15") (pintype "passive"))
      (node (ref "U101") (pin "21") (pinfunction "GND_21") (pintype "passive"))
      (node (ref "U101") (pin "3") (pinfunction "RFGND_3") (pintype "passive"))
      (node (ref "U101") (pin "4") (pinfunction "LPI_4") (pintype "passive"))
      (node (ref "U102") (pin "1") (pinfunction "GND_1") (pintype "passive"))
      (node (ref "Y100") (pin "3") (pinfunction "3_3") (pintype "passive"))
    )
    (net (code "36") (name "Net-(BUZ1-Pad2)") (class "Default")
      (node (ref "BUZ1") (pin "2") (pinfunction "2_2") (pintype "passive"))
      (node (ref "P2") (pin "1") (pinfunction "1_1") (pintype "passive"))
      (node (ref "Q100") (pin "3") (pinfunction "3_3") (pintype "passive"))
    )
    (net (code "37") (name "Net-(C104-Pad2)") (class "Default")
      (node (ref "C104") (pin "2") (pinfunction "2_2") (pintype "passive"))
      (node (ref "J100") (pin "1") (pinfunction "1_1") (pintype "passive"))
      (node (ref "JP100") (pin "1") (pinfunction "1_1") (pintype "passive"))
      (node (ref "L100") (pin "1") (pinfunction "1_1") (pintype "passive"))
    )
    (net (code "38") (name "Net-(C108-Pad1)") (class "Default")
      (node (ref "C108") (pin "1") (pinfunction "1_1") (pintype "passive"))
      (node (ref "U103") (pin "3") (pinfunction "3_3") (pintype "passive"))
    )
    (net (code "39") (name "Net-(C108-Pad2)") (class "Default")
      (node (ref "C108") (pin "2") (pinfunction "2_2") (pintype "passive"))
      (node (ref "L101") (pin "1") (pinfunction "1_1") (pintype "passive"))
    )
    (net (code "40") (name "Net-(C109-Pad1)") (class "Default")
      (node (ref "C109") (pin "1") (pinfunction "1_1") (pintype "passive"))
      (node (ref "U103") (pin "6") (pinfunction "6_6") (pintype "passive"))
    )
    (net (code "41") (name "Net-(C109-Pad2)") (class "Default")
      (node (ref "C109") (pin "2") (pinfunction "2_2") (pintype "passive"))
      (node (ref "L102") (pin "1") (pinfunction "1_1") (pintype "passive"))
    )
    (net (code "42") (name "Net-(D101-A)") (class "Default")
      (node (ref "D101") (pin "2") (pinfunction "A_2") (pintype "passive"))
      (node (ref "Q101") (pin "3") (pinfunction "3_3") (pintype "passive"))
      (node (ref "U103") (pin "1") (pinfunction "T1_1") (pintype "passive"))
    )
    (net (code "43") (name "Net-(D102-K)") (class "Default")
      (node (ref "D102") (pin "1") (pinfunction "K_1") (pintype "passive"))
      (node (ref "R137") (pin "2") (pinfunction "2_2") (pintype "passive"))
    )
    (net (code "44") (name "Net-(D103-K)") (class "Default")
      (node (ref "D103") (pin "1") (pinfunction "K_1") (pintype "passive"))
      (node (ref "R138") (pin "2") (pinfunction "2_2") (pintype "passive"))
    )
    (net (code "45") (name "Net-(P100-Pad2)") (class "Default")
      (node (ref "P100") (pin "2") (pinfunction "2_2") (pintype "passive"))
      (node (ref "R126") (pin "1") (pinfunction "1_1") (pintype "passive"))
    )
    (net (code "46") (name "Net-(Q1-D)") (class "Default")
      (node (ref "Q1") (pin "3") (pinfunction "D_3") (pintype "passive"))
      (node (ref "R125") (pin "2") (pinfunction "2_2") (pintype "passive"))
      (node (ref "R126") (pin "2") (pinfunction "2_2") (pintype "passive"))
      (node (ref "R129") (pin "2") (pinfunction "2_2") (pintype "passive"))
    )
    (net (code "47") (name "Net-(Q100-Pad1)") (class "Default")
      (node (ref "Q100") (pin "1") (pinfunction "1_1") (pintype "passive"))
      (node (ref "R130") (pin "2") (pinfunction "2_2") (pintype "passive"))
      (node (ref "R131") (pin "2") (pinfunction "2_2") (pintype "passive"))
    )
    (net (code "48") (name "Net-(Q101-Pad1)") (class "Default")
      (node (ref "Q101") (pin "1") (pinfunction "1_1") (pintype "passive"))
      (node (ref "R135") (pin "2") (pinfunction "2_2") (pintype "passive"))
      (node (ref "R136") (pin "2") (pinfunction "2_2") (pintype "passive"))
    )
    (net (code "49") (name "Net-(U100-GP0)") (class "Default")
      (node (ref "R139") (pin "1") (pinfunction "1_1") (pintype "passive"))
      (node (ref "U100") (pin "1") (pinfunction "GP0_1") (pintype "bidirectional"))
    )
    (net (code "50") (name "Net-(U100-GP1)") (class "Default")
      (node (ref "R140") (pin "1") (pinfunction "1_1") (pintype "passive"))
      (node (ref "U100") (pin "2") (pinfunction "GP1_2") (pintype "bidirectional"))
    )
    (net (code "51") (name "Net-(U100-GP2)") (class "Default")
      (node (ref "R141") (pin "1") (pinfunction "1_1") (pintype "passive"))
      (node (ref "U100") (pin "4") (pinfunction "GP2_4") (pintype "bidirectional"))
    )
    (net (code "52") (name "Net-(U100-GP3)") (class "Default")
      (node (ref "R142") (pin "1") (pinfunction "1_1") (pintype "passive"))
      (node (ref "U100") (pin "5") (pinfunction "GP3_5") (pintype "bidirectional"))
    )
    (net (code "53") (name "Net-(U100-GP4)") (class "Default")
      (node (ref "R100") (pin "1") (pinfunction "1_1") (pintype "passive"))
      (node (ref "U100") (pin "6") (pinfunction "GP4_6") (pintype "bidirectional"))
    )
    (net (code "54") (name "Net-(U100-GP5)") (class "Default")
      (node (ref "R101") (pin "1") (pinfunction "1_1") (pintype "passive"))
      (node (ref "U100") (pin "7") (pinfunction "GP5_7") (pintype "bidirectional"))
    )
    (net (code "55") (name "Net-(U100-GP6)") (class "Default")
      (node (ref "R114") (pin "1") (pinfunction "1_1") (pintype "passive"))
      (node (ref "U100") (pin "9") (pinfunction "GP6_9") (pintype "bidirectional"))
    )
    (net (code "56") (name "Net-(U100-GP7)") (class "Default")
      (node (ref "R104") (pin "1") (pinfunction "1_1") (pintype "passive"))
      (node (ref "U100") (pin "10") (pinfunction "GP7_10") (pintype "bidirectional"))
    )
    (net (code "57") (name "Net-(U100-GP8)") (class "Default")
      (node (ref "R106") (pin "1") (pinfunction "1_1") (pintype "passive"))
      (node (ref "U100") (pin "11") (pinfunction "GP8_11") (pintype "bidirectional"))
    )
    (net (code "58") (name "Net-(U100-GP9)") (class "Default")
      (node (ref "R108") (pin "1") (pinfunction "1_1") (pintype "passive"))
      (node (ref "U100") (pin "12") (pinfunction "GP9_12") (pintype "bidirectional"))
    )
    (net (code "59") (name "Net-(U100-GP10)") (class "Default")
      (node (ref "R111") (pin "1") (pinfunction "1_1") (pintype "passive"))
      (node (ref "U100") (pin "14") (pinfunction "GP10_14") (pintype "bidirectional"))
    )
    (net (code "60") (name "Net-(U100-GP11)") (class "Default")
      (node (ref "R113") (pin "1") (pinfunction "1_1") (pintype "passive"))
      (node (ref "U100") (pin "15") (pinfunction "GP11_15") (pintype "bidirectional"))
    )
    (net (code "61") (name "Net-(U100-GP12)") (class "Default")
      (node (ref "R105") (pin "1") (pinfunction "1_1") (pintype "passive"))
      (node (ref "U100") (pin "16") (pinfunction "GP12_16") (pintype "bidirectional"))
    )
    (net (code "62") (name "Net-(U100-GP13)") (class "Default")
      (node (ref "R112") (pin "1") (pinfunction "1_1") (pintype "passive"))
      (node (ref "U100") (pin "17") (pinfunction "GP13_17") (pintype "bidirectional"))
    )
    (net (code "63") (name "Net-(U100-GP14)") (class "Default")
      (node (ref "R109") (pin "1") (pinfunction "1_1") (pintype "passive"))
      (node (ref "U100") (pin "19") (pinfunction "GP14_19") (pintype "bidirectional"))
    )
    (net (code "64") (name "Net-(U100-GP15)") (class "Default")
      (node (ref "R110") (pin "1") (pinfunction "1_1") (pintype "passive"))
      (node (ref "U100") (pin "20") (pinfunction "GP15_20") (pintype "bidirectional"))
    )
    (net (code "65") (name "Net-(U100-GP19)") (class "Default")
      (node (ref "R144") (pin "2") (pinfunction "2_2") (pintype "passive"))
      (node (ref "U100") (pin "25") (pinfunction "GP19_25") (pintype "bidirectional"))
    )
    (net (code "66") (name "Net-(U100-GP20)") (class "Default")
      (node (ref "R102") (pin "2") (pinfunction "2_2") (pintype "passive"))
      (node (ref "U100") (pin "26") (pinfunction "GP20_26") (pintype "bidirectional"))
    )
    (net (code "67") (name "Net-(U100-GP22)") (class "Default")
      (node (ref "R143") (pin "2") (pinfunction "2_2") (pintype "passive"))
      (node (ref "U100") (pin "29") (pinfunction "GP22_29") (pintype "bidirectional"))
    )
    (net (code "68") (name "Net-(U100-GP26)") (class "Default")
      (node (ref "R133") (pin "2") (pinfunction "2_2") (pintype "passive"))
      (node (ref "U100") (pin "31") (pinfunction "GP26_31") (pintype "bidirectional"))
    )
    (net (code "69") (name "Net-(U100-GP27)") (class "Default")
      (node (ref "R132") (pin "2") (pinfunction "2_2") (pintype "passive"))
      (node (ref "U100") (pin "32") (pinfunction "GP27_32") (pintype "bidirectional"))
    )
    (net (code "70") (name "Net-(U100-GP28)") (class "Default")
      (node (ref "R107") (pin "2") (pinfunction "2_2") (pintype "passive"))
      (node (ref "U100") (pin "34") (pinfunction "GP28_34") (pintype "bidirectional"))
    )
    (net (code "71") (name "Net-(U100-RUN)") (class "Default")
      (node (ref "R103") (pin "2") (pinfunction "2_2") (pintype "passive"))
      (node (ref "U100") (pin "30") (pinfunction "RUN_30") (pintype "input"))
    )
    (net (code "72") (name "Net-(U101-FMIP)") (class "Default")
      (node (ref "C104") (pin "1") (pinfunction "1_1") (pintype "passive"))
      (node (ref "U101") (pin "2") (pinfunction "FMIP_2") (pintype "passive"))
    )
    (net (code "73") (name "Net-(U101-GPIO1)") (class "Default")
      (node (ref "TP101") (pin "1") (pinfunction "1_1") (pintype "passive"))
      (node (ref "U101") (pin "19") (pinfunction "GPIO1_19") (pintype "passive"))
    )
    (net (code "74") (name "Net-(U101-GPIO2)") (class "Default")
      (node (ref "TP100") (pin "1") (pinfunction "1_1") (pintype "passive"))
      (node (ref "U101") (pin "18") (pinfunction "GPIO2_18") (pintype "passive"))
    )
    (net (code "75") (name "Net-(U101-GPIO3)") (class "Default")
      (node (ref "C111") (pin "2") (pinfunction "2_2") (pintype "passive"))
      (node (ref "U101") (pin "17") (pinfunction "GPIO3_17") (pintype "passive"))
      (node (ref "Y100") (pin "2") (pinfunction "2_2") (pintype "passive"))
    )
    (net (code "76") (name "Net-(U101-RCLK)") (class "Default")
      (node (ref "C110") (pin "2") (pinfunction "2_2") (pintype "passive"))
      (node (ref "U101") (pin "9") (pinfunction "RCLK_9") (pintype "passive"))
      (node (ref "Y100") (pin "1") (pinfunction "1_1") (pintype "passive"))
    )
    (net (code "77") (name "Net-(U101-SCLK)") (class "Default")
      (node (ref "R119") (pin "2") (pinfunction "2_2") (pintype "passive"))
      (node (ref "R123") (pin "1") (pinfunction "1_1") (pintype "passive"))
      (node (ref "U101") (pin "7") (pinfunction "SCLK_7") (pintype "passive"))
    )
    (net (code "78") (name "Net-(U101-SDIO)") (class "Default")
      (node (ref "R118") (pin "2") (pinfunction "2_2") (pintype "passive"))
      (node (ref "R124") (pin "1") (pinfunction "1_1") (pintype "passive"))
      (node (ref "U101") (pin "8") (pinfunction "SDIO_8") (pintype "passive"))
    )
    (net (code "79") (name "Net-(U101-~{RST})") (class "Default")
      (node (ref "R121") (pin "2") (pinfunction "2_2") (pintype "passive"))
      (node (ref "R122") (pin "1") (pinfunction "1_1") (pintype "passive"))
      (node (ref "U101") (pin "5") (pinfunction "~{RST}_5") (pintype "passive"))
    )
    (net (code "80") (name "Net-(U101-~{SEN})") (class "Default")
      (node (ref "R120") (pin "2") (pinfunction "2_2") (pintype "passive"))
      (node (ref "U101") (pin "6") (pinfunction "~{SEN}_6") (pintype "passive"))
    )
    (net (code "81") (name "Net-(U102-DQ)") (class "Default")
      (node (ref "R125") (pin "1") (pinfunction "1_1") (pintype "passive"))
      (node (ref "U102") (pin "2") (pinfunction "DQ_2") (pintype "passive"))
    )
    (net (code "82") (name "unconnected-(P100-Pad3)") (class "Default")
      (node (ref "P100") (pin "3") (pinfunction "3_3") (pintype "passive+no_connect"))
    )
    (net (code "83") (name "unconnected-(P105-Pad1)") (class "Default")
      (node (ref "P105") (pin "1") (pinfunction "1_1") (pintype "passive"))
    )
    (net (code "84") (name "unconnected-(P105-Pad2)") (class "Default")
      (node (ref "P105") (pin "2") (pinfunction "2_2") (pintype "passive"))
    )
    (net (code "85") (name "unconnected-(P105-Pad3)") (class "Default")
      (node (ref "P105") (pin "3") (pinfunction "3_3") (pintype "passive"))
    )
    (net (code "86") (name "unconnected-(P108-Pad2)") (class "Default")
      (node (ref "P108") (pin "2") (pinfunction "2_2") (pintype "passive"))
    )
    (net (code "87") (name "unconnected-(P108-Pad3)") (class "Default")
      (node (ref "P108") (pin "3") (pinfunction "3_3") (pintype "passive"))
    )
    (net (code "88") (name "unconnected-(U100-AVREF-Pad35)") (class "Default")
      (node (ref "U100") (pin "35") (pinfunction "AVREF_35") (pintype "power_in+no_connect"))
    )
    (net (code "89") (name "unconnected-(U100-EN-Pad37)") (class "Default")
      (node (ref "U100") (pin "37") (pinfunction "EN_37") (pintype "input+no_connect"))
    )
    (net (code "90") (name "unconnected-(U100-SWCLK-Pad41)") (class "Default")
      (node (ref "U100") (pin "41") (pinfunction "SWCLK_41") (pintype "bidirectional+no_connect"))
    )
    (net (code "91") (name "unconnected-(U100-SWDIO-Pad43)") (class "Default")
      (node (ref "U100") (pin "43") (pinfunction "SWDIO_43") (pintype "bidirectional+no_connect"))
    )
    (net (code "92") (name "unconnected-(U100-VSYS-Pad39)") (class "Default")
      (node (ref "U100") (pin "39") (pinfunction "VSYS_39") (pintype "power_in+no_connect"))
    )
  )
)
